# miib.net
KiCad netlist of a schematic drawn in EAGLE
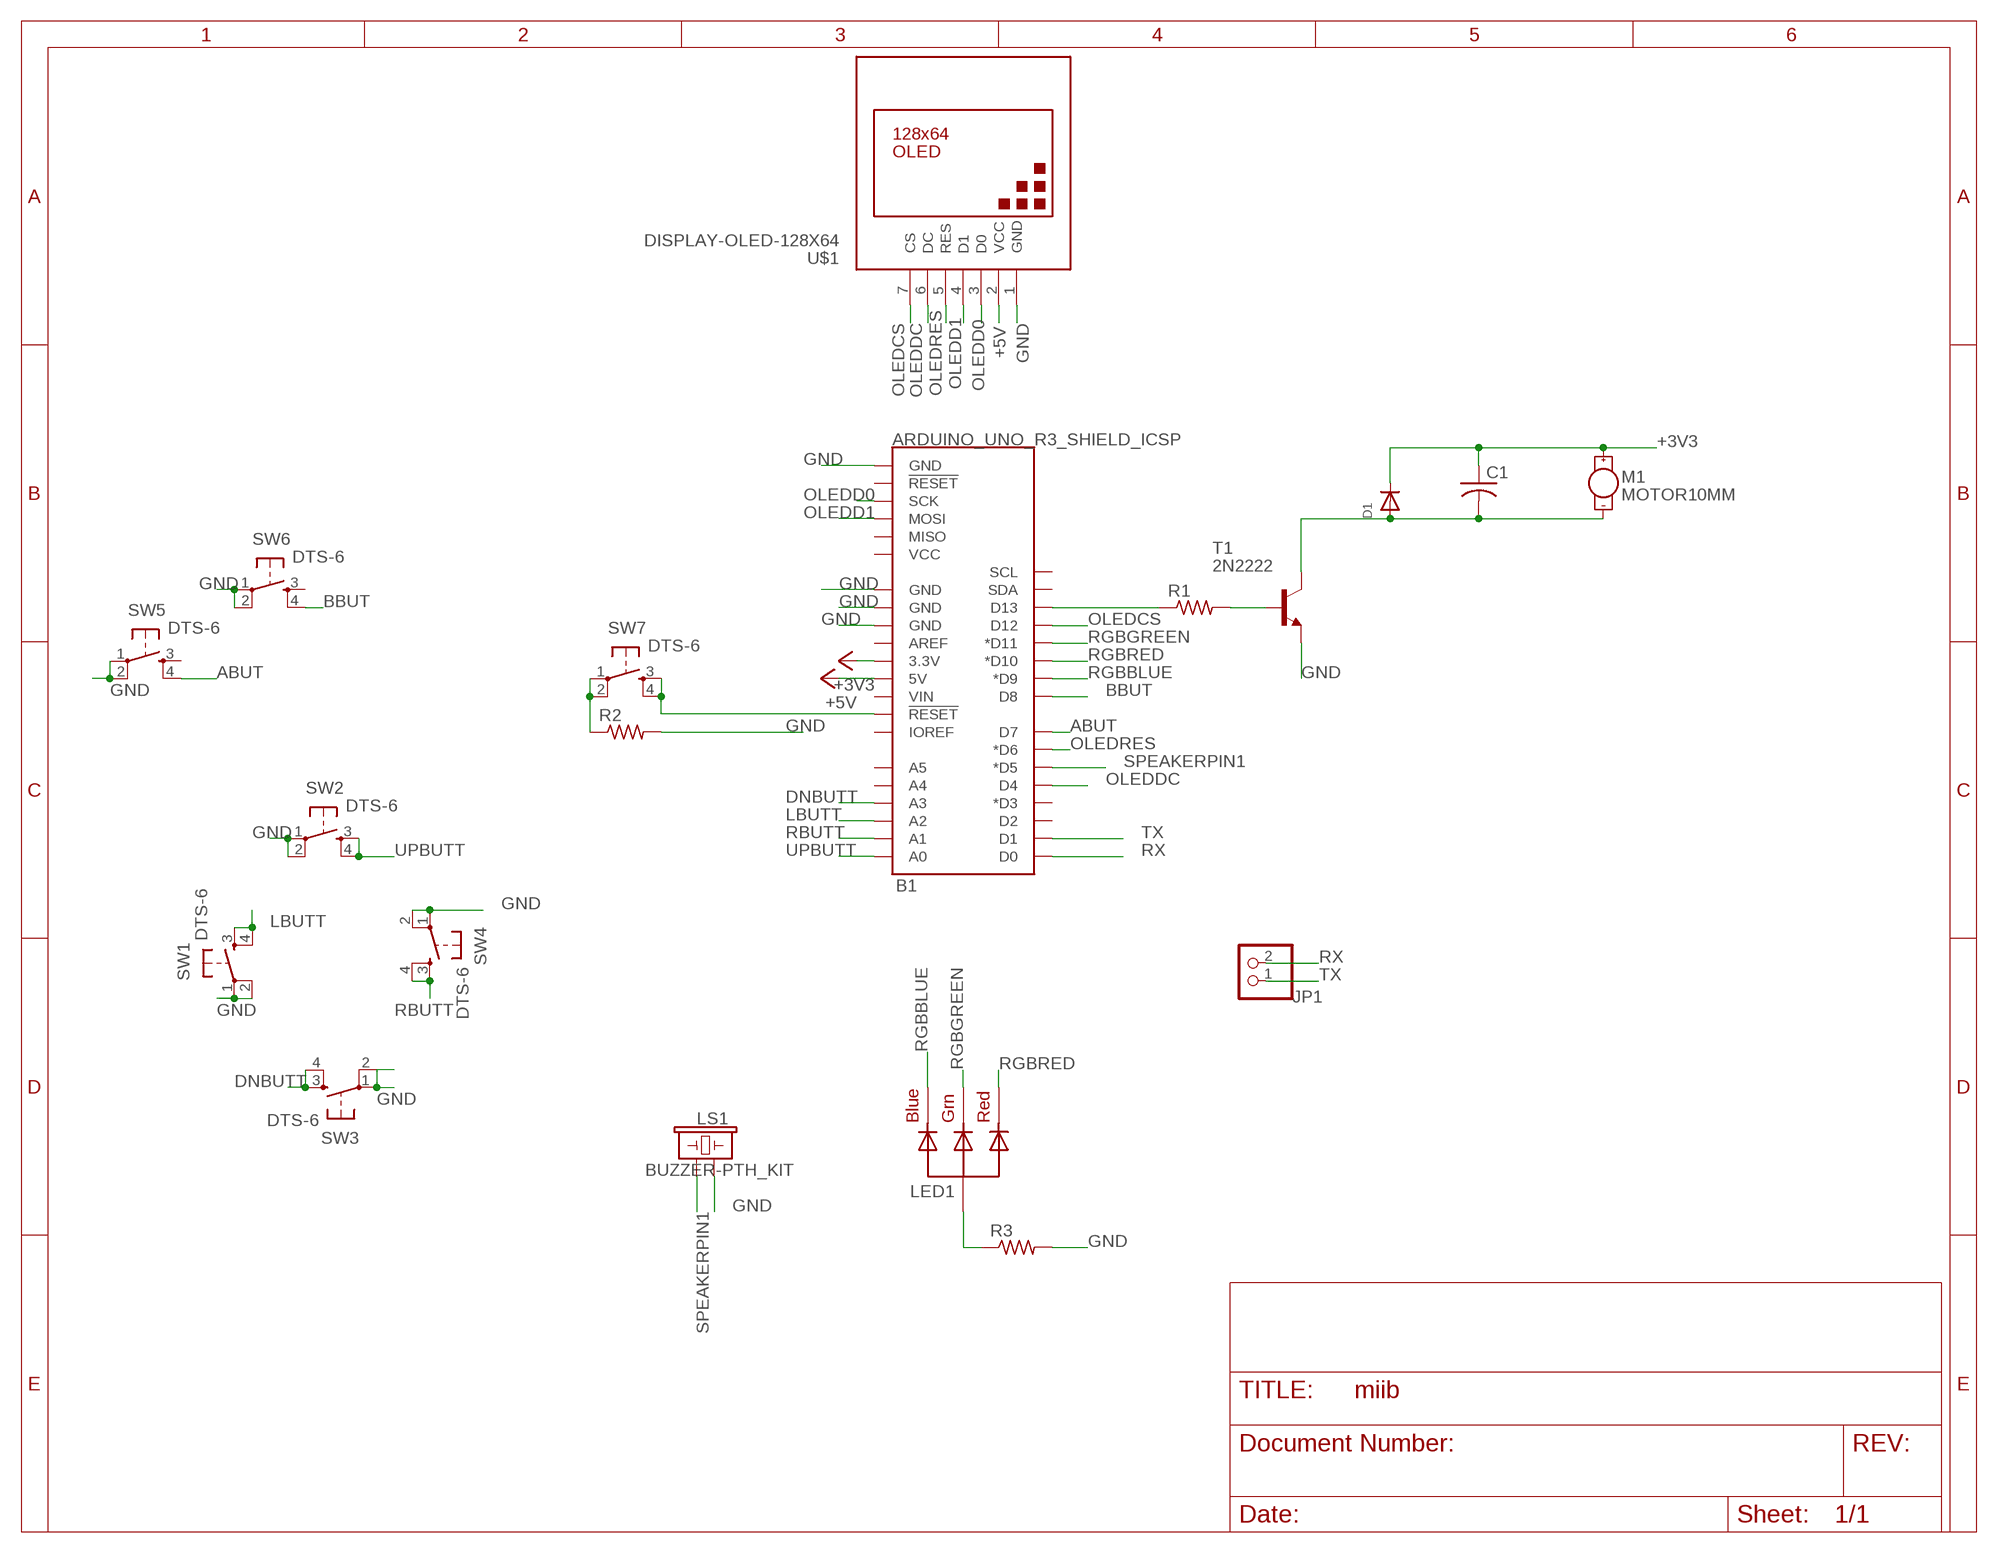
[diagram p0: schematic, sheet 1]

(export (version "E")
  (design (tool "Eeschema 10.0.6"))
  (components
    (comp (ref "B1")
      (value "ARDUINO_UNO_R3_SHIELD_ICSP")
      (footprint "eagle-import:UNO_R3_SHIELD_ICSP")
      (libsource (lib "eagle-import") (part "ARDUINO_UNO_R3_SHIELD_ICSP"))
    )
    (comp (ref "C1")
      (value "C-US025-025X050")
      (footprint "eagle-import:C025-025X050")
      (libsource (lib "eagle-import") (part "C-US025-025X050"))
    )
    (comp (ref "D1")
      (value "DIODEDO-1N4148")
      (footprint "eagle-import:DO-1N4148")
      (libsource (lib "eagle-import") (part "DIODEDO-1N4148"))
    )
    (comp (ref "JP1")
      (value "PINHD-1X2/90")
      (footprint "eagle-import:1X02_90")
      (libsource (lib "eagle-import") (part "PINHD-1X2/90"))
    )
    (comp (ref "LED1")
      (value "RGBLED_CA-5MM")
      (footprint "eagle-import:LED5MMRGB")
      (libsource (lib "eagle-import") (part "RGBLED_CA-5MM"))
    )
    (comp (ref "LS1")
      (value "BUZZER-PTH_KIT")
      (footprint "eagle-import:BUZZER-12MM-KIT")
      (libsource (lib "eagle-import") (part "BUZZER-PTH_KIT"))
    )
    (comp (ref "M1")
      (value "MOTOR10MM")
      (footprint "eagle-import:VIBE-MOTOR-10MM")
      (libsource (lib "eagle-import") (part "MOTOR10MM"))
    )
    (comp (ref "R1")
      (value "R-US_0204/7")
      (footprint "eagle-import:0204_7")
      (libsource (lib "eagle-import") (part "R-US_0204/7"))
    )
    (comp (ref "R2")
      (value "R-US_0204/7")
      (footprint "eagle-import:0204_7")
      (libsource (lib "eagle-import") (part "R-US_0204/7"))
    )
    (comp (ref "R3")
      (value "R-US_0204/7")
      (footprint "eagle-import:0204_7")
      (libsource (lib "eagle-import") (part "R-US_0204/7"))
    )
    (comp (ref "SW1")
      (value "DTS-6")
      (footprint "eagle-import:DTS-6")
      (libsource (lib "eagle-import") (part "DTS-6"))
    )
    (comp (ref "SW2")
      (value "DTS-6")
      (footprint "eagle-import:DTS-6")
      (libsource (lib "eagle-import") (part "DTS-6"))
    )
    (comp (ref "SW3")
      (value "DTS-6")
      (footprint "eagle-import:DTS-6")
      (libsource (lib "eagle-import") (part "DTS-6"))
    )
    (comp (ref "SW4")
      (value "DTS-6")
      (footprint "eagle-import:DTS-6")
      (libsource (lib "eagle-import") (part "DTS-6"))
    )
    (comp (ref "SW5")
      (value "DTS-6")
      (footprint "eagle-import:DTS-6")
      (libsource (lib "eagle-import") (part "DTS-6"))
    )
    (comp (ref "SW6")
      (value "DTS-6")
      (footprint "eagle-import:DTS-6")
      (libsource (lib "eagle-import") (part "DTS-6"))
    )
    (comp (ref "SW7")
      (value "DTS-6")
      (footprint "eagle-import:DTS-6")
      (libsource (lib "eagle-import") (part "DTS-6"))
    )
    (comp (ref "T1")
      (value "2N2222")
      (footprint "eagle-import:TO92-EBC-OVAL")
      (libsource (lib "eagle-import") (part "2N2222"))
    )
    (comp (ref "U$1")
      (value "DISPLAY-OLED-128X64")
      (footprint "eagle-import:DISPLAY-OLED-128X64")
      (libsource (lib "eagle-import") (part "DISPLAY-OLED-128X64"))
    )
  )
  (nets
    (net (code "1") (name "+3V3") (class "Default")
      (node (ref "B1") (pin "3.3V") (pinfunction "3.3V_3.3V") (pintype "bidirectional"))
      (node (ref "C1") (pin "1") (pinfunction "1_1") (pintype "passive"))
      (node (ref "D1") (pin "C") (pinfunction "C_C") (pintype "passive"))
      (node (ref "M1") (pin "+") (pinfunction "+_+") (pintype "bidirectional"))
    )
    (net (code "2") (name "+5V") (class "Default")
      (node (ref "B1") (pin "5V") (pinfunction "5V_5V") (pintype "bidirectional"))
      (node (ref "U$1") (pin "2") (pinfunction "VCC_2") (pintype "power_in"))
    )
    (net (code "3") (name "/ABUT") (class "Default")
      (node (ref "B1") (pin "D7") (pinfunction "D7_D7") (pintype "bidirectional"))
      (node (ref "SW5") (pin "4") (pinfunction "4_4") (pintype "passive"))
    )
    (net (code "4") (name "/BBUT") (class "Default")
      (node (ref "B1") (pin "D8") (pinfunction "D8_D8") (pintype "bidirectional"))
      (node (ref "SW6") (pin "4") (pinfunction "4_4") (pintype "passive"))
    )
    (net (code "5") (name "/DNBUTT") (class "Default")
      (node (ref "B1") (pin "A3") (pinfunction "A3_A3") (pintype "bidirectional"))
      (node (ref "SW3") (pin "3") (pinfunction "3_3") (pintype "passive"))
      (node (ref "SW3") (pin "4") (pinfunction "4_4") (pintype "passive"))
    )
    (net (code "6") (name "/GND") (class "Default")
      (node (ref "B1") (pin "GND@0") (pinfunction "GND_GND@0") (pintype "bidirectional"))
      (node (ref "B1") (pin "GND@1") (pinfunction "GND_GND@1") (pintype "bidirectional"))
      (node (ref "B1") (pin "GND@2") (pinfunction "GND_GND@2") (pintype "bidirectional"))
      (node (ref "B1") (pin "GND_ICSP") (pinfunction "GND_GND_ICSP") (pintype "bidirectional"))
      (node (ref "LS1") (pin "-") (pinfunction "2_-") (pintype "passive"))
      (node (ref "R2") (pin "2") (pinfunction "2_2") (pintype "passive"))
      (node (ref "R3") (pin "2") (pinfunction "2_2") (pintype "passive"))
      (node (ref "SW1") (pin "1") (pinfunction "1_1") (pintype "passive"))
      (node (ref "SW1") (pin "2") (pinfunction "2_2") (pintype "passive"))
      (node (ref "SW2") (pin "1") (pinfunction "1_1") (pintype "passive"))
      (node (ref "SW2") (pin "2") (pinfunction "2_2") (pintype "passive"))
      (node (ref "SW3") (pin "1") (pinfunction "1_1") (pintype "passive"))
      (node (ref "SW3") (pin "2") (pinfunction "2_2") (pintype "passive"))
      (node (ref "SW4") (pin "1") (pinfunction "1_1") (pintype "passive"))
      (node (ref "SW4") (pin "2") (pinfunction "2_2") (pintype "passive"))
      (node (ref "SW5") (pin "1") (pinfunction "1_1") (pintype "passive"))
      (node (ref "SW5") (pin "2") (pinfunction "2_2") (pintype "passive"))
      (node (ref "SW6") (pin "1") (pinfunction "1_1") (pintype "passive"))
      (node (ref "SW6") (pin "2") (pinfunction "2_2") (pintype "passive"))
      (node (ref "T1") (pin "E") (pinfunction "E_E") (pintype "passive"))
      (node (ref "U$1") (pin "1") (pinfunction "GND_1") (pintype "power_in"))
    )
    (net (code "7") (name "/LBUTT") (class "Default")
      (node (ref "B1") (pin "A2") (pinfunction "A2_A2") (pintype "bidirectional"))
      (node (ref "SW1") (pin "3") (pinfunction "3_3") (pintype "passive"))
      (node (ref "SW1") (pin "4") (pinfunction "4_4") (pintype "passive"))
    )
    (net (code "8") (name "/OLEDCS") (class "Default")
      (node (ref "B1") (pin "D12") (pinfunction "D12_D12") (pintype "bidirectional"))
      (node (ref "U$1") (pin "7") (pinfunction "CS_7") (pintype "bidirectional"))
    )
    (net (code "9") (name "/OLEDD0") (class "Default")
      (node (ref "B1") (pin "SCK") (pinfunction "SCK_SCK") (pintype "bidirectional"))
      (node (ref "U$1") (pin "3") (pinfunction "D0_3") (pintype "bidirectional"))
    )
    (net (code "10") (name "/OLEDD1") (class "Default")
      (node (ref "B1") (pin "MOSI") (pinfunction "MOSI_MOSI") (pintype "bidirectional"))
      (node (ref "U$1") (pin "4") (pinfunction "D1_4") (pintype "bidirectional"))
    )
    (net (code "11") (name "/OLEDDC") (class "Default")
      (node (ref "B1") (pin "D4") (pinfunction "D4_D4") (pintype "bidirectional"))
      (node (ref "U$1") (pin "6") (pinfunction "DC_6") (pintype "bidirectional"))
    )
    (net (code "12") (name "/OLEDRES") (class "Default")
      (node (ref "B1") (pin "D6") (pinfunction "*D6_D6") (pintype "bidirectional"))
      (node (ref "U$1") (pin "5") (pinfunction "RES_5") (pintype "bidirectional"))
    )
    (net (code "13") (name "/RBUTT") (class "Default")
      (node (ref "B1") (pin "A1") (pinfunction "A1_A1") (pintype "bidirectional"))
      (node (ref "SW4") (pin "3") (pinfunction "3_3") (pintype "passive"))
      (node (ref "SW4") (pin "4") (pinfunction "4_4") (pintype "passive"))
    )
    (net (code "14") (name "/RGBBLUE") (class "Default")
      (node (ref "B1") (pin "D9") (pinfunction "*D9_D9") (pintype "bidirectional"))
      (node (ref "LED1") (pin "4") (pinfunction "BLUE_4") (pintype "bidirectional"))
    )
    (net (code "15") (name "/RGBGREEN") (class "Default")
      (node (ref "B1") (pin "D11") (pinfunction "*D11_D11") (pintype "bidirectional"))
      (node (ref "LED1") (pin "3") (pinfunction "GREEN_3") (pintype "bidirectional"))
    )
    (net (code "16") (name "/RGBRED") (class "Default")
      (node (ref "B1") (pin "D10") (pinfunction "*D10_D10") (pintype "bidirectional"))
      (node (ref "LED1") (pin "1") (pinfunction "RED_1") (pintype "bidirectional"))
    )
    (net (code "17") (name "/RX") (class "Default")
      (node (ref "B1") (pin "RX") (pinfunction "D0_RX") (pintype "bidirectional"))
      (node (ref "JP1") (pin "2") (pinfunction "2_2") (pintype "passive"))
    )
    (net (code "18") (name "/SPEAKERPIN1") (class "Default")
      (node (ref "B1") (pin "D5") (pinfunction "*D5_D5") (pintype "bidirectional"))
      (node (ref "LS1") (pin "+") (pinfunction "1_+") (pintype "passive"))
    )
    (net (code "19") (name "/TX") (class "Default")
      (node (ref "B1") (pin "TX") (pinfunction "D1_TX") (pintype "bidirectional"))
      (node (ref "JP1") (pin "1") (pinfunction "1_1") (pintype "passive"))
    )
    (net (code "20") (name "/UPBUTT") (class "Default")
      (node (ref "B1") (pin "A0") (pinfunction "A0_A0") (pintype "bidirectional"))
      (node (ref "SW2") (pin "3") (pinfunction "3_3") (pintype "passive"))
      (node (ref "SW2") (pin "4") (pinfunction "4_4") (pintype "passive"))
    )
    (net (code "21") (name "Net-(B1-PadD13)") (class "Default")
      (node (ref "B1") (pin "D13") (pinfunction "D13_D13") (pintype "bidirectional"))
      (node (ref "R1") (pin "1") (pinfunction "1_1") (pintype "passive"))
    )
    (net (code "22") (name "Net-(B1-~{RESET}-PadRES)") (class "Default")
      (node (ref "B1") (pin "RES") (pinfunction "~{RESET}_RES") (pintype "bidirectional"))
      (node (ref "SW7") (pin "3") (pinfunction "3_3") (pintype "passive"))
      (node (ref "SW7") (pin "4") (pinfunction "4_4") (pintype "passive"))
    )
    (net (code "23") (name "Net-(C1-Pad2)") (class "Default")
      (node (ref "C1") (pin "2") (pinfunction "2_2") (pintype "passive"))
      (node (ref "D1") (pin "A") (pinfunction "A_A") (pintype "passive"))
      (node (ref "M1") (pin "-") (pinfunction "-_-") (pintype "bidirectional"))
      (node (ref "T1") (pin "C") (pinfunction "C_C") (pintype "passive"))
    )
    (net (code "24") (name "Net-(LED1-VCC)") (class "Default")
      (node (ref "LED1") (pin "2") (pinfunction "VCC_2") (pintype "bidirectional"))
      (node (ref "R3") (pin "1") (pinfunction "1_1") (pintype "passive"))
    )
    (net (code "25") (name "Net-(R1-Pad2)") (class "Default")
      (node (ref "R1") (pin "2") (pinfunction "2_2") (pintype "passive"))
      (node (ref "T1") (pin "B") (pinfunction "B_B") (pintype "passive"))
    )
    (net (code "26") (name "Net-(R2-Pad1)") (class "Default")
      (node (ref "R2") (pin "1") (pinfunction "1_1") (pintype "passive"))
      (node (ref "SW7") (pin "1") (pinfunction "1_1") (pintype "passive"))
      (node (ref "SW7") (pin "2") (pinfunction "2_2") (pintype "passive"))
    )
    (net (code "27") (name "unconnected-(B1-*D3-PadD3)") (class "Default")
      (node (ref "B1") (pin "D3") (pinfunction "*D3_D3") (pintype "bidirectional"))
    )
    (net (code "28") (name "unconnected-(B1-PadA4)") (class "Default")
      (node (ref "B1") (pin "A4") (pinfunction "A4_A4") (pintype "bidirectional"))
    )
    (net (code "29") (name "unconnected-(B1-PadA5)") (class "Default")
      (node (ref "B1") (pin "A5") (pinfunction "A5_A5") (pintype "bidirectional"))
    )
    (net (code "30") (name "unconnected-(B1-PadAREF)") (class "Default")
      (node (ref "B1") (pin "AREF") (pinfunction "AREF_AREF") (pintype "bidirectional"))
    )
    (net (code "31") (name "unconnected-(B1-PadD2)") (class "Default")
      (node (ref "B1") (pin "D2") (pinfunction "D2_D2") (pintype "bidirectional"))
    )
    (net (code "32") (name "unconnected-(B1-PadIOREF)") (class "Default")
      (node (ref "B1") (pin "IOREF") (pinfunction "IOREF_IOREF") (pintype "bidirectional"))
    )
    (net (code "33") (name "unconnected-(B1-PadMISO)") (class "Default")
      (node (ref "B1") (pin "MISO") (pinfunction "MISO_MISO") (pintype "bidirectional"))
    )
    (net (code "34") (name "unconnected-(B1-PadSCL)") (class "Default")
      (node (ref "B1") (pin "SCL") (pinfunction "SCL_SCL") (pintype "bidirectional"))
    )
    (net (code "35") (name "unconnected-(B1-PadSDA)") (class "Default")
      (node (ref "B1") (pin "SDA") (pinfunction "SDA_SDA") (pintype "bidirectional"))
    )
    (net (code "36") (name "unconnected-(B1-PadVIN)") (class "Default")
      (node (ref "B1") (pin "VIN") (pinfunction "VIN_VIN") (pintype "bidirectional"))
    )
    (net (code "37") (name "unconnected-(B1-VCC-Pad5V_ICSP)") (class "Default")
      (node (ref "B1") (pin "5V_ICSP") (pinfunction "VCC_5V_ICSP") (pintype "bidirectional"))
    )
    (net (code "38") (name "unconnected-(B1-~{RESET}-PadRST_ICSP)") (class "Default")
      (node (ref "B1") (pin "RST_ICSP") (pinfunction "~{RESET}_RST_ICSP") (pintype "bidirectional"))
    )
    (net (code "39") (name "unconnected-(SW5-Pad3)") (class "Default")
      (node (ref "SW5") (pin "3") (pinfunction "3_3") (pintype "passive"))
    )
    (net (code "40") (name "unconnected-(SW6-Pad3)") (class "Default")
      (node (ref "SW6") (pin "3") (pinfunction "3_3") (pintype "passive"))
    )
  )
)
